# Phototransistor_Mount.net
KiCad netlist of a schematic drawn in EAGLE
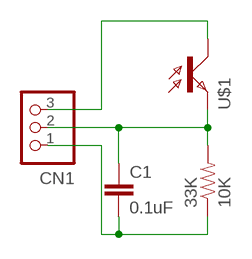
[diagram p0: schematic, sheet 1]

(export (version "E")
  (design (tool "Eeschema 10.0.6"))
  (components
    (comp (ref "33K")
      (value "10K")
      (footprint "eagle-import:0603-RES")
      (libsource (lib "eagle-import") (part "RESISTOR0603-RES"))
    )
    (comp (ref "C1")
      (value "0.1uF")
      (footprint "eagle-import:0603-CAP")
      (libsource (lib "eagle-import") (part "CAP0603-CAP"))
    )
    (comp (ref "CN1")
      (value "B3B-PH-K-S")
      (footprint "eagle-import:B3B-PH-K-S")
      (libsource (lib "eagle-import") (part "B3B-PH-K-S"))
    )
    (comp (ref "U$1")
      (value "ALS")
      (footprint "eagle-import:SMD")
      (libsource (lib "eagle-import") (part "ALS"))
    )
  )
  (nets
    (net (code "1") (name "Net-(33K-Pad1)") (class "Default")
      (node (ref "33K") (pin "1") (pinfunction "1_1") (pintype "passive"))
      (node (ref "C1") (pin "2") (pinfunction "2_2") (pintype "passive"))
      (node (ref "CN1") (pin "1") (pinfunction "1_1") (pintype "passive"))
    )
    (net (code "2") (name "Net-(33K-Pad2)") (class "Default")
      (node (ref "33K") (pin "2") (pinfunction "2_2") (pintype "passive"))
      (node (ref "C1") (pin "1") (pinfunction "1_1") (pintype "passive"))
      (node (ref "CN1") (pin "2") (pinfunction "2_2") (pintype "passive"))
      (node (ref "U$1") (pin "E") (pinfunction "E_E") (pintype "passive"))
    )
    (net (code "3") (name "Net-(CN1-Pad3)") (class "Default")
      (node (ref "CN1") (pin "3") (pinfunction "3_3") (pintype "passive"))
      (node (ref "U$1") (pin "C") (pinfunction "C_C") (pintype "passive"))
    )
  )
)
